# Schematic_v2.net
KiCad netlist of a schematic drawn in Altium Designer
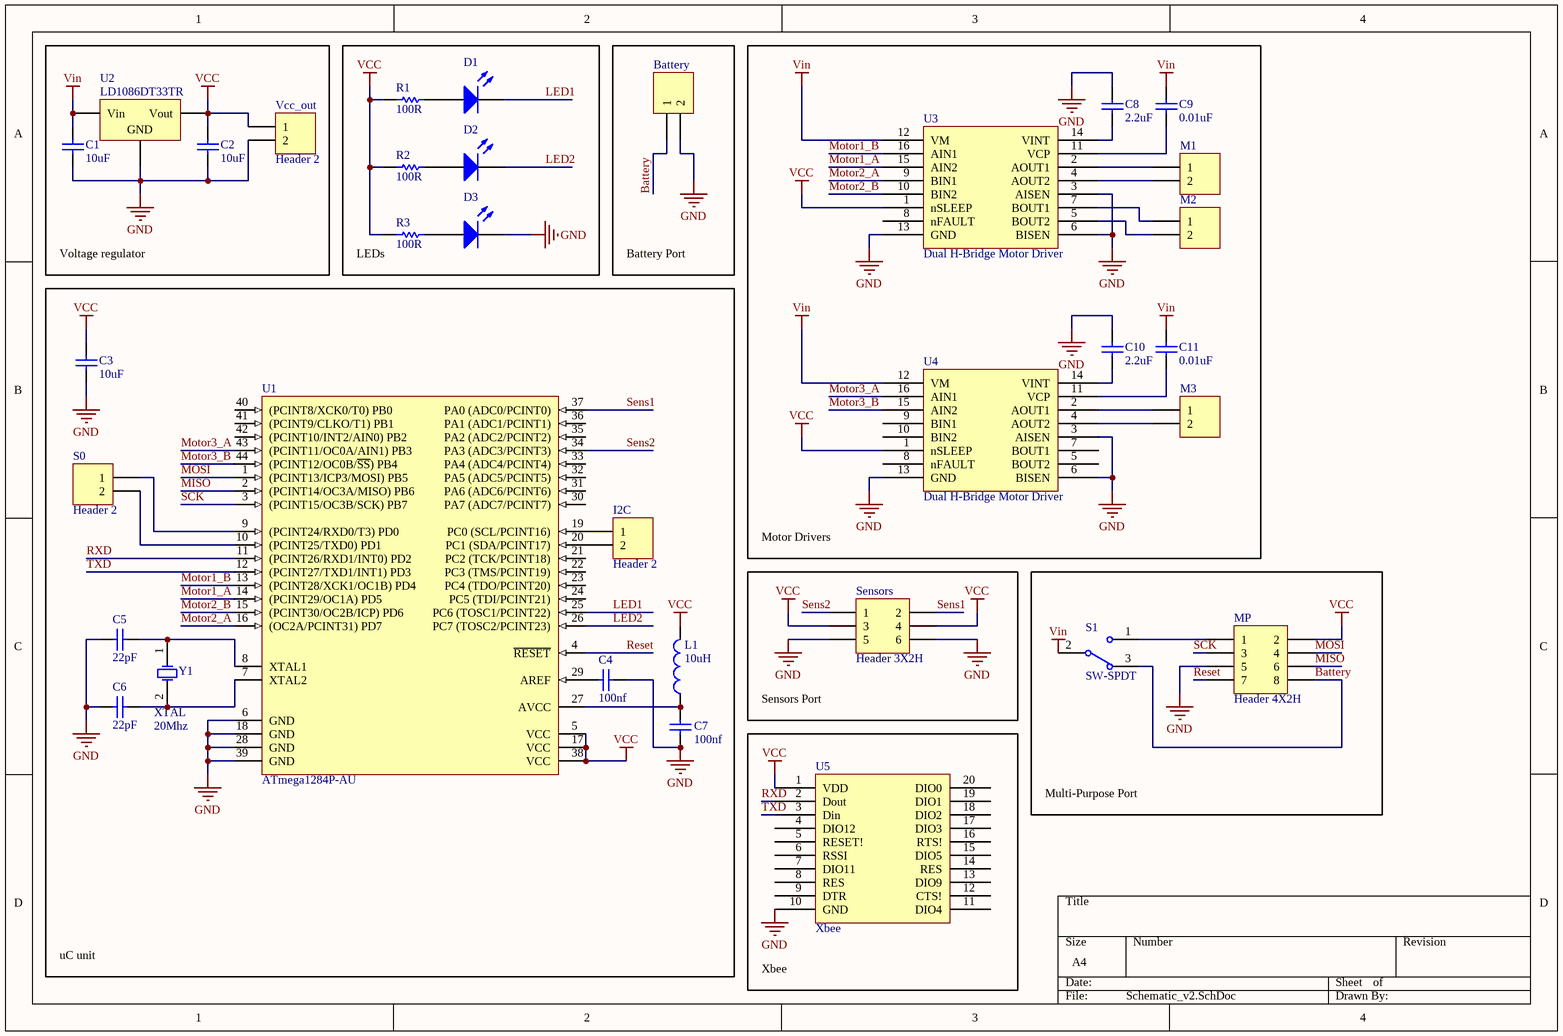
[diagram p0: Schematic_v2.SchDoc]

(export (version "E")
  (design (tool "Eeschema 10.0.6"))
  (components
    (comp (ref "Battery")
      (value "Header 2")
      (footprint "Terminal_2_p3.5")
      (description "Header, 2-Pin")
      (fields (field (name "PUBLISHER") "Altium Limited"))
      (libsource (lib "") (part "Header 2_2"))
    )
    (comp (ref "C1")
      (value "10uF")
      (footprint "C1206")
      (description "Capacitor")
      (fields (field (name "Comment") "Cap") (field (name "PUBLISHER") "Altium Limited"))
      (libsource (lib "Miscellaneous Devices") (part "Cap"))
    )
    (comp (ref "C2")
      (value "10uF")
      (footprint "C1206")
      (description "Capacitor")
      (fields (field (name "Comment") "Cap") (field (name "PUBLISHER") "Altium Limited"))
      (libsource (lib "Miscellaneous Devices") (part "Cap"))
    )
    (comp (ref "C3")
      (value "10uF")
      (footprint "C1206")
      (description "Capacitor")
      (fields (field (name "Comment") "Cap") (field (name "PUBLISHER") "Altium Limited"))
      (libsource (lib "Miscellaneous Devices") (part "Cap"))
    )
    (comp (ref "C4")
      (value "100nf")
      (footprint "C1206")
      (description "Capacitor")
      (fields (field (name "Comment") "Cap") (field (name "PUBLISHER") "Altium Limited"))
      (libsource (lib "Miscellaneous Devices") (part "Cap"))
    )
    (comp (ref "C5")
      (value "22pF")
      (footprint "C1206")
      (description "Capacitor")
      (fields (field (name "Comment") "Cap") (field (name "PUBLISHER") "Altium Limited"))
      (libsource (lib "Miscellaneous Devices") (part "Cap"))
    )
    (comp (ref "C6")
      (value "22pF")
      (footprint "C1206")
      (description "Capacitor")
      (fields (field (name "Comment") "Cap") (field (name "PUBLISHER") "Altium Limited"))
      (libsource (lib "Miscellaneous Devices") (part "Cap"))
    )
    (comp (ref "C7")
      (value "100nf")
      (footprint "C1206")
      (description "Capacitor")
      (fields (field (name "Comment") "Cap") (field (name "PUBLISHER") "Altium Limited"))
      (libsource (lib "Miscellaneous Devices") (part "Cap"))
    )
    (comp (ref "C8")
      (value "2.2uF")
      (footprint "C1206")
      (description "Capacitor")
      (fields (field (name "Comment") "Cap") (field (name "PUBLISHER") "Altium Limited"))
      (libsource (lib "Miscellaneous Devices") (part "Cap"))
    )
    (comp (ref "C9")
      (value "0.01uF")
      (footprint "C1206")
      (description "Capacitor")
      (fields (field (name "Comment") "Cap") (field (name "PUBLISHER") "Altium Limited"))
      (libsource (lib "Miscellaneous Devices") (part "Cap"))
    )
    (comp (ref "C10")
      (value "2.2uF")
      (footprint "C1206")
      (description "Capacitor")
      (fields (field (name "Comment") "Cap") (field (name "PUBLISHER") "Altium Limited"))
      (libsource (lib "Miscellaneous Devices") (part "Cap"))
    )
    (comp (ref "C11")
      (value "0.01uF")
      (footprint "C1206")
      (description "Capacitor")
      (fields (field (name "Comment") "Cap") (field (name "PUBLISHER") "Altium Limited"))
      (libsource (lib "Miscellaneous Devices") (part "Cap"))
    )
    (comp (ref "D1")
      (value "LED0")
      (footprint "1206")
      (description "Typical INFRARED GaAs LED")
      (fields (field (name "PUBLISHER") "Altium Limited"))
      (libsource (lib "Miscellaneous Devices") (part "LED0"))
    )
    (comp (ref "D2")
      (value "LED0")
      (footprint "1206")
      (description "Typical INFRARED GaAs LED")
      (fields (field (name "PUBLISHER") "Altium Limited"))
      (libsource (lib "Miscellaneous Devices") (part "LED0"))
    )
    (comp (ref "D3")
      (value "LED0")
      (footprint "1206")
      (description "Typical INFRARED GaAs LED")
      (fields (field (name "PUBLISHER") "Altium Limited"))
      (libsource (lib "Miscellaneous Devices") (part "LED0"))
    )
    (comp (ref "I2C")
      (value "Header 2")
      (footprint "HDR1X2")
      (description "Header, 2-Pin")
      (fields (field (name "PUBLISHER") "Altium Limited"))
      (libsource (lib "Miscellaneous Connectors") (part "Header 2"))
    )
    (comp (ref "L1")
      (value "10uH")
      (footprint "C1206")
      (description "Inductor")
      (fields (field (name "PUBLISHER") "Altium Limited"))
      (libsource (lib "Miscellaneous Devices") (part "Inductor"))
    )
    (comp (ref "M1")
      (value "Header 2")
      (footprint "Terminal_2_p3.5")
      (description "Header, 2-Pin")
      (fields (field (name "PUBLISHER") "Altium Limited"))
      (libsource (lib "Miscellaneous Connectors") (part "Header 2"))
    )
    (comp (ref "M2")
      (value "Header 2")
      (footprint "Terminal_2_p3.5")
      (description "Header, 2-Pin")
      (fields (field (name "PUBLISHER") "Altium Limited"))
      (libsource (lib "Miscellaneous Connectors") (part "Header 2"))
    )
    (comp (ref "M3")
      (value "Header 2")
      (footprint "Terminal_2_p3.5")
      (description "Header, 2-Pin")
      (fields (field (name "PUBLISHER") "Altium Limited"))
      (libsource (lib "Miscellaneous Connectors") (part "Header 2"))
    )
    (comp (ref "MP")
      (value "Header 4X2H")
      (footprint "HDR2X4H")
      (description "Header, 4-Pin, Dual row, Right Angle")
      (fields (field (name "PUBLISHER") "Altium Limited"))
      (libsource (lib "Miscellaneous Connectors") (part "Header 4X2H"))
    )
    (comp (ref "R1")
      (value "100R")
      (footprint "8-1206")
      (description "Resistor")
      (fields (field (name "Comment") "Res1") (field (name "PUBLISHER") "Altium Limited"))
      (libsource (lib "Miscellaneous Devices") (part "Res1"))
    )
    (comp (ref "R2")
      (value "100R")
      (footprint "8-1206")
      (description "Resistor")
      (fields (field (name "Comment") "Res1") (field (name "PUBLISHER") "Altium Limited"))
      (libsource (lib "Miscellaneous Devices") (part "Res1"))
    )
    (comp (ref "R3")
      (value "100R")
      (footprint "8-1206")
      (description "Resistor")
      (fields (field (name "Comment") "Res1") (field (name "PUBLISHER") "Altium Limited"))
      (libsource (lib "Miscellaneous Devices") (part "Res1"))
    )
    (comp (ref "S0")
      (value "Header 2")
      (footprint "HDR1X2")
      (description "Header, 2-Pin")
      (fields (field (name "PUBLISHER") "Altium Limited"))
      (libsource (lib "") (part "Header 2_1"))
    )
    (comp (ref "S1")
      (value "SW-SPDT")
      (footprint "Switch_SPDT")
      (description "SPDT Subminiature Toggle Switch, Right Angle Mounting, Vertical Actuation")
      (fields (field (name "PUBLISHER") "Altium Limited"))
      (libsource (lib "Miscellaneous Devices") (part "SW-SPDT"))
    )
    (comp (ref "Sensors")
      (value "Header 3X2H")
      (footprint "HDR2X3H")
      (description "Header, 3-Pin, Dual row, Right Angle")
      (fields (field (name "PUBLISHER") "Altium Limited"))
      (libsource (lib "Miscellaneous Connectors") (part "Header 3X2H"))
    )
    (comp (ref "U1")
      (value "ATmega1284P-AU")
      (footprint "44A_N")
      (description "20 MHz 8-bit AVR Microcontroller with 128KB Flash, 44-Pin TQFP Pkg, Industrial Temp")
      (fields (field (name "PUBLISHER") "Altium Limited"))
      (libsource (lib "Atmel Communication ICs") (part "ATmega1284P-AU"))
    )
    (comp (ref "U2")
      (value "LD1086DT33TR")
      (footprint "TO-252AA_M")
      (description "Voltage Regulator")
      (fields (field (name "PUBLISHER") "Altium Limited"))
      (libsource (lib "Miscellaneous Devices") (part "Volt Reg"))
    )
    (comp (ref "U3")
      (value "Dual H-Bridge Motor Driver")
      (footprint "TSSOP16_M")
      (libsource (lib "MySchLib") (part "DRV8833"))
    )
    (comp (ref "U4")
      (value "Dual H-Bridge Motor Driver")
      (footprint "TSSOP16_M")
      (libsource (lib "MySchLib") (part "DRV8833"))
    )
    (comp (ref "U5") (value "Xbee") (footprint "Xbee_DIP") (libsource (lib "MySchLib") (part "Xbee")))
    (comp (ref "Vcc_out")
      (value "Header 2")
      (footprint "HDR1X2")
      (description "Header, 2-Pin")
      (fields (field (name "PUBLISHER") "Altium Limited"))
      (libsource (lib "Miscellaneous Connectors") (part "Header 2"))
    )
    (comp (ref "Y1")
      (value "XTAL")
      (footprint "ECX-64A")
      (description "Crystal")
      (fields (field (name "FREQUENCY") "20Mhz") (field (name "PUBLISHER") "Altium Limited"))
      (libsource (lib "Miscellaneous Devices") (part "XTAL"))
    )
  )
  (nets
    (net (code "1") (name "/Battery") (class "Default")
      (node (ref "Battery") (pin "1") (pinfunction "1_1") (pintype "passive"))
      (node (ref "MP") (pin "8") (pinfunction "8_8") (pintype "passive"))
      (node (ref "S1") (pin "3") (pinfunction "3_3") (pintype "passive"))
    )
    (net (code "2") (name "/LED1") (class "Default")
      (node (ref "D1") (pin "2") (pinfunction "K_2") (pintype "passive"))
      (node (ref "U1") (pin "25") (pinfunction "PC6_(TOSC1/PCINT22)_25") (pintype "input"))
    )
    (net (code "3") (name "/LED2") (class "Default")
      (node (ref "D2") (pin "2") (pinfunction "K_2") (pintype "passive"))
      (node (ref "U1") (pin "26") (pinfunction "PC7_(TOSC2/PCINT23)_26") (pintype "input"))
    )
    (net (code "4") (name "/MISO") (class "Default")
      (node (ref "MP") (pin "6") (pinfunction "6_6") (pintype "passive"))
      (node (ref "U1") (pin "2") (pinfunction "(PCINT14/OC3A/MISO)_PB6_2") (pintype "input"))
    )
    (net (code "5") (name "/MOSI") (class "Default")
      (node (ref "MP") (pin "4") (pinfunction "4_4") (pintype "passive"))
      (node (ref "U1") (pin "1") (pinfunction "(PCINT13/ICP3/MOSI)_PB5_1") (pintype "input"))
    )
    (net (code "6") (name "/Motor1_A") (class "Default")
      (node (ref "U1") (pin "14") (pinfunction "(PCINT29/OC1A)_PD5_14") (pintype "input"))
      (node (ref "U3") (pin "15") (pinfunction "AIN2_15") (pintype "passive"))
    )
    (net (code "7") (name "/Motor1_B") (class "Default")
      (node (ref "U1") (pin "13") (pinfunction "(PCINT28/XCK1/OC1B)_PD4_13") (pintype "input"))
      (node (ref "U3") (pin "16") (pinfunction "AIN1_16") (pintype "passive"))
    )
    (net (code "8") (name "/Motor2_A") (class "Default")
      (node (ref "U1") (pin "16") (pinfunction "(OC2A/PCINT31)_PD7_16") (pintype "input"))
      (node (ref "U3") (pin "9") (pinfunction "BIN1_9") (pintype "passive"))
    )
    (net (code "9") (name "/Motor2_B") (class "Default")
      (node (ref "U1") (pin "15") (pinfunction "(PCINT30/OC2B/ICP)_PD6_15") (pintype "input"))
      (node (ref "U3") (pin "10") (pinfunction "BIN2_10") (pintype "passive"))
    )
    (net (code "10") (name "/Motor3_A") (class "Default")
      (node (ref "U1") (pin "43") (pinfunction "(PCINT11/OC0A/AIN1)_PB3_43") (pintype "input"))
      (node (ref "U4") (pin "16") (pinfunction "AIN1_16") (pintype "passive"))
    )
    (net (code "11") (name "/Motor3_B") (class "Default")
      (node (ref "U1") (pin "44") (pinfunction "(PCINT12/OC0B/~{SS})_PB4_44") (pintype "input"))
      (node (ref "U4") (pin "15") (pinfunction "AIN2_15") (pintype "passive"))
    )
    (net (code "12") (name "/RXD") (class "Default")
      (node (ref "U1") (pin "11") (pinfunction "(PCINT26/RXD1/INT0)_PD2_11") (pintype "input"))
      (node (ref "U5") (pin "2") (pinfunction "Dout_2") (pintype "passive"))
    )
    (net (code "13") (name "/Reset") (class "Default")
      (node (ref "MP") (pin "7") (pinfunction "7_7") (pintype "passive"))
      (node (ref "U1") (pin "4") (pinfunction "~{RESET}_4") (pintype "input"))
    )
    (net (code "14") (name "/SCK") (class "Default")
      (node (ref "MP") (pin "3") (pinfunction "3_3") (pintype "passive"))
      (node (ref "U1") (pin "3") (pinfunction "(PCINT15/OC3B/SCK)_PB7_3") (pintype "input"))
    )
    (net (code "15") (name "/Sens1") (class "Default")
      (node (ref "Sensors") (pin "2") (pinfunction "2_2") (pintype "passive"))
      (node (ref "U1") (pin "37") (pinfunction "PA0_(ADC0/PCINT0)_37") (pintype "input"))
    )
    (net (code "16") (name "/Sens2") (class "Default")
      (node (ref "Sensors") (pin "1") (pinfunction "1_1") (pintype "passive"))
      (node (ref "U1") (pin "34") (pinfunction "PA3_(ADC3/PCINT3)_34") (pintype "input"))
    )
    (net (code "17") (name "/TXD") (class "Default")
      (node (ref "U1") (pin "12") (pinfunction "(PCINT27/TXD1/INT1)_PD3_12") (pintype "input"))
      (node (ref "U5") (pin "3") (pinfunction "Din_3") (pintype "passive"))
    )
    (net (code "18") (name "GND") (class "Default")
      (node (ref "Battery") (pin "2") (pinfunction "2_2") (pintype "passive"))
      (node (ref "C1") (pin "1") (pinfunction "1_1") (pintype "passive"))
      (node (ref "C10") (pin "2") (pinfunction "2_2") (pintype "passive"))
      (node (ref "C2") (pin "1") (pinfunction "1_1") (pintype "passive"))
      (node (ref "C3") (pin "1") (pinfunction "1_1") (pintype "passive"))
      (node (ref "C4") (pin "2") (pinfunction "2_2") (pintype "passive"))
      (node (ref "C5") (pin "1") (pinfunction "1_1") (pintype "passive"))
      (node (ref "C6") (pin "1") (pinfunction "1_1") (pintype "passive"))
      (node (ref "C7") (pin "1") (pinfunction "1_1") (pintype "passive"))
      (node (ref "C8") (pin "2") (pinfunction "2_2") (pintype "passive"))
      (node (ref "D3") (pin "2") (pinfunction "K_2") (pintype "passive"))
      (node (ref "MP") (pin "5") (pinfunction "5_5") (pintype "passive"))
      (node (ref "Sensors") (pin "5") (pinfunction "5_5") (pintype "passive"))
      (node (ref "Sensors") (pin "6") (pinfunction "6_6") (pintype "passive"))
      (node (ref "U1") (pin "18") (pinfunction "GND_18") (pintype "passive"))
      (node (ref "U1") (pin "28") (pinfunction "GND_28") (pintype "passive"))
      (node (ref "U1") (pin "39") (pinfunction "GND_39") (pintype "passive"))
      (node (ref "U1") (pin "6") (pinfunction "GND_6") (pintype "passive"))
      (node (ref "U2") (pin "2") (pinfunction "GND_2") (pintype "passive"))
      (node (ref "U3") (pin "13") (pinfunction "GND_13") (pintype "passive"))
      (node (ref "U3") (pin "3") (pinfunction "AISEN_3") (pintype "passive"))
      (node (ref "U3") (pin "6") (pinfunction "BISEN_6") (pintype "passive"))
      (node (ref "U4") (pin "13") (pinfunction "GND_13") (pintype "passive"))
      (node (ref "U4") (pin "3") (pinfunction "AISEN_3") (pintype "passive"))
      (node (ref "U4") (pin "6") (pinfunction "BISEN_6") (pintype "passive"))
      (node (ref "U5") (pin "10") (pinfunction "GND_10") (pintype "passive"))
      (node (ref "Vcc_out") (pin "2") (pinfunction "2_2") (pintype "passive"))
    )
    (net (code "19") (name "Net-(D1-A)") (class "Default")
      (node (ref "D1") (pin "1") (pinfunction "A_1") (pintype "passive"))
      (node (ref "R1") (pin "2") (pinfunction "2_2") (pintype "passive"))
    )
    (net (code "20") (name "Net-(D2-A)") (class "Default")
      (node (ref "D2") (pin "1") (pinfunction "A_1") (pintype "passive"))
      (node (ref "R2") (pin "2") (pinfunction "2_2") (pintype "passive"))
    )
    (net (code "21") (name "Net-(D3-A)") (class "Default")
      (node (ref "D3") (pin "1") (pinfunction "A_1") (pintype "passive"))
      (node (ref "R3") (pin "2") (pinfunction "2_2") (pintype "passive"))
    )
    (net (code "22") (name "Net-(MP-Pad1)") (class "Default")
      (node (ref "MP") (pin "1") (pinfunction "1_1") (pintype "passive"))
      (node (ref "S1") (pin "1") (pinfunction "1_1") (pintype "passive"))
    )
    (net (code "23") (name "Net-(U1-(PCINT24{slash}RXD0{slash}T3)_PD0)") (class "Default")
      (node (ref "S0") (pin "1") (pinfunction "1_1") (pintype "passive"))
      (node (ref "U1") (pin "9") (pinfunction "(PCINT24/RXD0/T3)_PD0_9") (pintype "input"))
    )
    (net (code "24") (name "Net-(U1-(PCINT25{slash}TXD0)_PD1)") (class "Default")
      (node (ref "S0") (pin "2") (pinfunction "2_2") (pintype "passive"))
      (node (ref "U1") (pin "10") (pinfunction "(PCINT25/TXD0)_PD1_10") (pintype "input"))
    )
    (net (code "25") (name "Net-(U1-AREF)") (class "Default")
      (node (ref "C4") (pin "1") (pinfunction "1_1") (pintype "passive"))
      (node (ref "U1") (pin "29") (pinfunction "AREF_29") (pintype "input"))
    )
    (net (code "26") (name "Net-(U1-AVCC)") (class "Default")
      (node (ref "C7") (pin "2") (pinfunction "2_2") (pintype "passive"))
      (node (ref "L1") (pin "1") (pinfunction "1_1") (pintype "passive"))
      (node (ref "U1") (pin "27") (pinfunction "AVCC_27") (pintype "passive"))
    )
    (net (code "27") (name "Net-(U1-PC0_(SCL{slash}PCINT16))") (class "Default")
      (node (ref "I2C") (pin "1") (pinfunction "1_1") (pintype "passive"))
      (node (ref "U1") (pin "19") (pinfunction "PC0_(SCL/PCINT16)_19") (pintype "input"))
    )
    (net (code "28") (name "Net-(U1-PC1_(SDA{slash}PCINT17))") (class "Default")
      (node (ref "I2C") (pin "2") (pinfunction "2_2") (pintype "passive"))
      (node (ref "U1") (pin "20") (pinfunction "PC1_(SDA/PCINT17)_20") (pintype "input"))
    )
    (net (code "29") (name "Net-(U1-XTAL1)") (class "Default")
      (node (ref "C5") (pin "2") (pinfunction "2_2") (pintype "passive"))
      (node (ref "U1") (pin "8") (pinfunction "XTAL1_8") (pintype "passive"))
      (node (ref "Y1") (pin "1") (pinfunction "OSC1_1") (pintype "passive"))
    )
    (net (code "30") (name "Net-(U1-XTAL2)") (class "Default")
      (node (ref "C6") (pin "2") (pinfunction "2_2") (pintype "passive"))
      (node (ref "U1") (pin "7") (pinfunction "XTAL2_7") (pintype "passive"))
      (node (ref "Y1") (pin "2") (pinfunction "OSC2_2") (pintype "passive"))
    )
    (net (code "31") (name "Net-(U3-AOUT1)") (class "Default")
      (node (ref "M1") (pin "1") (pinfunction "1_1") (pintype "passive"))
      (node (ref "U3") (pin "2") (pinfunction "AOUT1_2") (pintype "passive"))
    )
    (net (code "32") (name "Net-(U3-AOUT2)") (class "Default")
      (node (ref "M1") (pin "2") (pinfunction "2_2") (pintype "passive"))
      (node (ref "U3") (pin "4") (pinfunction "AOUT2_4") (pintype "passive"))
    )
    (net (code "33") (name "Net-(U3-BOUT1)") (class "Default")
      (node (ref "M2") (pin "1") (pinfunction "1_1") (pintype "passive"))
      (node (ref "U3") (pin "7") (pinfunction "BOUT1_7") (pintype "passive"))
    )
    (net (code "34") (name "Net-(U3-BOUT2)") (class "Default")
      (node (ref "M2") (pin "2") (pinfunction "2_2") (pintype "passive"))
      (node (ref "U3") (pin "5") (pinfunction "BOUT2_5") (pintype "passive"))
    )
    (net (code "35") (name "Net-(U3-VCP)") (class "Default")
      (node (ref "C9") (pin "1") (pinfunction "1_1") (pintype "passive"))
      (node (ref "U3") (pin "11") (pinfunction "VCP_11") (pintype "passive"))
    )
    (net (code "36") (name "Net-(U3-VINT)") (class "Default")
      (node (ref "C8") (pin "1") (pinfunction "1_1") (pintype "passive"))
      (node (ref "U3") (pin "14") (pinfunction "VINT_14") (pintype "passive"))
    )
    (net (code "37") (name "Net-(U4-AOUT1)") (class "Default")
      (node (ref "M3") (pin "1") (pinfunction "1_1") (pintype "passive"))
      (node (ref "U4") (pin "2") (pinfunction "AOUT1_2") (pintype "passive"))
    )
    (net (code "38") (name "Net-(U4-AOUT2)") (class "Default")
      (node (ref "M3") (pin "2") (pinfunction "2_2") (pintype "passive"))
      (node (ref "U4") (pin "4") (pinfunction "AOUT2_4") (pintype "passive"))
    )
    (net (code "39") (name "Net-(U4-VCP)") (class "Default")
      (node (ref "C11") (pin "1") (pinfunction "1_1") (pintype "passive"))
      (node (ref "U4") (pin "11") (pinfunction "VCP_11") (pintype "passive"))
    )
    (net (code "40") (name "Net-(U4-VINT)") (class "Default")
      (node (ref "C10") (pin "1") (pinfunction "1_1") (pintype "passive"))
      (node (ref "U4") (pin "14") (pinfunction "VINT_14") (pintype "passive"))
    )
    (net (code "41") (name "VCC") (class "Default")
      (node (ref "C2") (pin "2") (pinfunction "2_2") (pintype "passive"))
      (node (ref "C3") (pin "2") (pinfunction "2_2") (pintype "passive"))
      (node (ref "L1") (pin "2") (pinfunction "2_2") (pintype "passive"))
      (node (ref "MP") (pin "2") (pinfunction "2_2") (pintype "passive"))
      (node (ref "R1") (pin "1") (pinfunction "1_1") (pintype "passive"))
      (node (ref "R2") (pin "1") (pinfunction "1_1") (pintype "passive"))
      (node (ref "R3") (pin "1") (pinfunction "1_1") (pintype "passive"))
      (node (ref "Sensors") (pin "3") (pinfunction "3_3") (pintype "passive"))
      (node (ref "Sensors") (pin "4") (pinfunction "4_4") (pintype "passive"))
      (node (ref "U1") (pin "17") (pinfunction "VCC_17") (pintype "passive"))
      (node (ref "U1") (pin "38") (pinfunction "VCC_38") (pintype "passive"))
      (node (ref "U1") (pin "5") (pinfunction "VCC_5") (pintype "passive"))
      (node (ref "U2") (pin "3") (pinfunction "Vout_3") (pintype "passive"))
      (node (ref "U3") (pin "1") (pinfunction "nSLEEP_1") (pintype "passive"))
      (node (ref "U4") (pin "1") (pinfunction "nSLEEP_1") (pintype "passive"))
      (node (ref "U5") (pin "1") (pinfunction "VDD_1") (pintype "passive"))
      (node (ref "Vcc_out") (pin "1") (pinfunction "1_1") (pintype "passive"))
    )
    (net (code "42") (name "Vin") (class "Default")
      (node (ref "C1") (pin "2") (pinfunction "2_2") (pintype "passive"))
      (node (ref "C11") (pin "2") (pinfunction "2_2") (pintype "passive"))
      (node (ref "C9") (pin "2") (pinfunction "2_2") (pintype "passive"))
      (node (ref "S1") (pin "2") (pinfunction "2_2") (pintype "passive"))
      (node (ref "U2") (pin "1") (pinfunction "Vin_1") (pintype "passive"))
      (node (ref "U3") (pin "12") (pinfunction "VM_12") (pintype "passive"))
      (node (ref "U4") (pin "12") (pinfunction "VM_12") (pintype "passive"))
    )
    (net (code "43") (name "unconnected-(U1-(PCINT8{slash}XCK0{slash}T0)_PB0-Pad40)") (class "Default")
      (node (ref "U1") (pin "40") (pinfunction "(PCINT8/XCK0/T0)_PB0_40") (pintype "input"))
    )
    (net (code "44") (name "unconnected-(U1-(PCINT9{slash}CLKO{slash}T1)_PB1-Pad41)") (class "Default")
      (node (ref "U1") (pin "41") (pinfunction "(PCINT9/CLKO/T1)_PB1_41") (pintype "input"))
    )
    (net (code "45") (name "unconnected-(U1-(PCINT10{slash}INT2{slash}AIN0)_PB2-Pad42)") (class "Default")
      (node (ref "U1") (pin "42") (pinfunction "(PCINT10/INT2/AIN0)_PB2_42") (pintype "input"))
    )
    (net (code "46") (name "unconnected-(U1-PA1_(ADC1{slash}PCINT1)-Pad36)") (class "Default")
      (node (ref "U1") (pin "36") (pinfunction "PA1_(ADC1/PCINT1)_36") (pintype "input"))
    )
    (net (code "47") (name "unconnected-(U1-PA2_(ADC2{slash}PCINT2)-Pad35)") (class "Default")
      (node (ref "U1") (pin "35") (pinfunction "PA2_(ADC2/PCINT2)_35") (pintype "input"))
    )
    (net (code "48") (name "unconnected-(U1-PA4_(ADC4{slash}PCINT4)-Pad33)") (class "Default")
      (node (ref "U1") (pin "33") (pinfunction "PA4_(ADC4/PCINT4)_33") (pintype "input"))
    )
    (net (code "49") (name "unconnected-(U1-PA5_(ADC5{slash}PCINT5)-Pad32)") (class "Default")
      (node (ref "U1") (pin "32") (pinfunction "PA5_(ADC5/PCINT5)_32") (pintype "input"))
    )
    (net (code "50") (name "unconnected-(U1-PA6_(ADC6{slash}PCINT6)-Pad31)") (class "Default")
      (node (ref "U1") (pin "31") (pinfunction "PA6_(ADC6/PCINT6)_31") (pintype "input"))
    )
    (net (code "51") (name "unconnected-(U1-PA7_(ADC7{slash}PCINT7)-Pad30)") (class "Default")
      (node (ref "U1") (pin "30") (pinfunction "PA7_(ADC7/PCINT7)_30") (pintype "input"))
    )
    (net (code "52") (name "unconnected-(U1-PC2_(TCK{slash}PCINT18)-Pad21)") (class "Default")
      (node (ref "U1") (pin "21") (pinfunction "PC2_(TCK/PCINT18)_21") (pintype "input"))
    )
    (net (code "53") (name "unconnected-(U1-PC3_(TMS{slash}PCINT19)-Pad22)") (class "Default")
      (node (ref "U1") (pin "22") (pinfunction "PC3_(TMS/PCINT19)_22") (pintype "input"))
    )
    (net (code "54") (name "unconnected-(U1-PC4_(TDO{slash}PCINT20)-Pad23)") (class "Default")
      (node (ref "U1") (pin "23") (pinfunction "PC4_(TDO/PCINT20)_23") (pintype "input"))
    )
    (net (code "55") (name "unconnected-(U1-PC5_(TDI{slash}PCINT21)-Pad24)") (class "Default")
      (node (ref "U1") (pin "24") (pinfunction "PC5_(TDI/PCINT21)_24") (pintype "input"))
    )
    (net (code "56") (name "unconnected-(U3-nFAULT-Pad8)") (class "Default")
      (node (ref "U3") (pin "8") (pinfunction "nFAULT_8") (pintype "passive"))
    )
    (net (code "57") (name "unconnected-(U4-BIN1-Pad9)") (class "Default")
      (node (ref "U4") (pin "9") (pinfunction "BIN1_9") (pintype "passive"))
    )
    (net (code "58") (name "unconnected-(U4-BIN2-Pad10)") (class "Default")
      (node (ref "U4") (pin "10") (pinfunction "BIN2_10") (pintype "passive"))
    )
    (net (code "59") (name "unconnected-(U4-BOUT1-Pad7)") (class "Default")
      (node (ref "U4") (pin "7") (pinfunction "BOUT1_7") (pintype "passive"))
    )
    (net (code "60") (name "unconnected-(U4-BOUT2-Pad5)") (class "Default")
      (node (ref "U4") (pin "5") (pinfunction "BOUT2_5") (pintype "passive"))
    )
    (net (code "61") (name "unconnected-(U4-nFAULT-Pad8)") (class "Default")
      (node (ref "U4") (pin "8") (pinfunction "nFAULT_8") (pintype "passive"))
    )
    (net (code "62") (name "unconnected-(U5-CTS!-Pad12)") (class "Default")
      (node (ref "U5") (pin "12") (pinfunction "CTS!_12") (pintype "passive"))
    )
    (net (code "63") (name "unconnected-(U5-DIO0-Pad20)") (class "Default")
      (node (ref "U5") (pin "20") (pinfunction "DIO0_20") (pintype "passive"))
    )
    (net (code "64") (name "unconnected-(U5-DIO1-Pad19)") (class "Default")
      (node (ref "U5") (pin "19") (pinfunction "DIO1_19") (pintype "passive"))
    )
    (net (code "65") (name "unconnected-(U5-DIO2-Pad18)") (class "Default")
      (node (ref "U5") (pin "18") (pinfunction "DIO2_18") (pintype "passive"))
    )
    (net (code "66") (name "unconnected-(U5-DIO3-Pad17)") (class "Default")
      (node (ref "U5") (pin "17") (pinfunction "DIO3_17") (pintype "passive"))
    )
    (net (code "67") (name "unconnected-(U5-DIO4-Pad11)") (class "Default")
      (node (ref "U5") (pin "11") (pinfunction "DIO4_11") (pintype "passive"))
    )
    (net (code "68") (name "unconnected-(U5-DIO5-Pad15)") (class "Default")
      (node (ref "U5") (pin "15") (pinfunction "DIO5_15") (pintype "passive"))
    )
    (net (code "69") (name "unconnected-(U5-DIO9-Pad13)") (class "Default")
      (node (ref "U5") (pin "13") (pinfunction "DIO9_13") (pintype "passive"))
    )
    (net (code "70") (name "unconnected-(U5-DIO11-Pad7)") (class "Default")
      (node (ref "U5") (pin "7") (pinfunction "DIO11_7") (pintype "passive"))
    )
    (net (code "71") (name "unconnected-(U5-DIO12-Pad4)") (class "Default")
      (node (ref "U5") (pin "4") (pinfunction "DIO12_4") (pintype "passive"))
    )
    (net (code "72") (name "unconnected-(U5-DTR-Pad9)") (class "Default")
      (node (ref "U5") (pin "9") (pinfunction "DTR_9") (pintype "passive"))
    )
    (net (code "73") (name "unconnected-(U5-RES-Pad8)") (class "Default")
      (node (ref "U5") (pin "8") (pinfunction "RES_8") (pintype "passive"))
    )
    (net (code "74") (name "unconnected-(U5-RES-Pad14)") (class "Default")
      (node (ref "U5") (pin "14") (pinfunction "RES_14") (pintype "passive"))
    )
    (net (code "75") (name "unconnected-(U5-RESET!-Pad5)") (class "Default")
      (node (ref "U5") (pin "5") (pinfunction "RESET!_5") (pintype "passive"))
    )
    (net (code "76") (name "unconnected-(U5-RSSI-Pad6)") (class "Default")
      (node (ref "U5") (pin "6") (pinfunction "RSSI_6") (pintype "passive"))
    )
    (net (code "77") (name "unconnected-(U5-RTS!-Pad16)") (class "Default")
      (node (ref "U5") (pin "16") (pinfunction "RTS!_16") (pintype "passive"))
    )
  )
)
